# ADC.net
KiCad netlist of a schematic drawn in Altium Designer
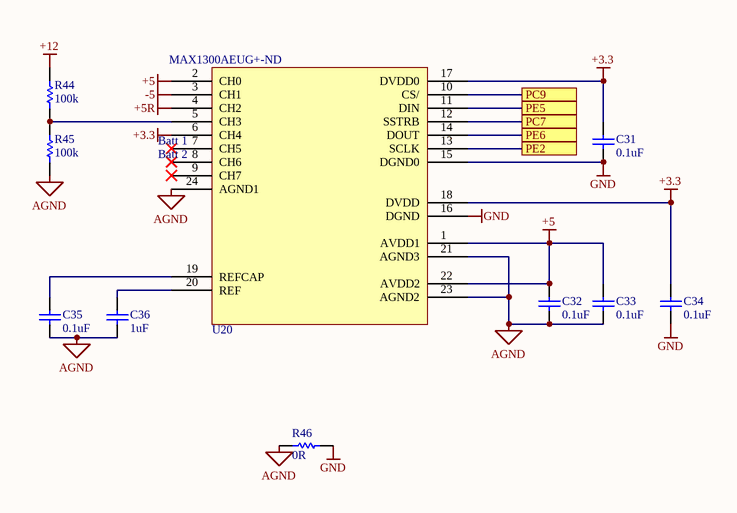
[diagram p0: ADC.SchDoc]

(export (version "E")
  (design (tool "Eeschema 10.0.6"))
  (components
    (comp (ref "C31")
      (value "0.1uF")
      (footprint "CAPC0402(1005)60_L")
      (description "CAP CER 0.1UF 10V X7R 0402")
      (fields
        (field (name "MANUFACTURER") "Murata Electronics North America")
        (field (name "MANUFACTURER PART NUMBER") "GRM155R71A104KA01D")
      )
      (libsource (lib "Altium Content Vault") (part "CMP-1034-00252-1"))
    )
    (comp (ref "C32")
      (value "0.1uF")
      (footprint "CAPC0402(1005)60_L")
      (description "CAP CER 0.1UF 10V X7R 0402")
      (fields
        (field (name "MANUFACTURER") "Murata Electronics North America")
        (field (name "MANUFACTURER PART NUMBER") "GRM155R71A104KA01D")
      )
      (libsource (lib "Altium Content Vault") (part "CMP-1034-00252-1"))
    )
    (comp (ref "C33")
      (value "0.1uF")
      (footprint "CAPC0402(1005)60_L")
      (description "CAP CER 0.1UF 10V X7R 0402")
      (fields
        (field (name "MANUFACTURER") "Murata Electronics North America")
        (field (name "MANUFACTURER PART NUMBER") "GRM155R71A104KA01D")
      )
      (libsource (lib "Altium Content Vault") (part "CMP-1034-00252-1"))
    )
    (comp (ref "C34")
      (value "0.1uF")
      (footprint "CAPC0402(1005)60_L")
      (description "CAP CER 0.1UF 10V X7R 0402")
      (fields
        (field (name "MANUFACTURER") "Murata Electronics North America")
        (field (name "MANUFACTURER PART NUMBER") "GRM155R71A104KA01D")
      )
      (libsource (lib "Altium Content Vault") (part "CMP-1034-00252-1"))
    )
    (comp (ref "C35")
      (value "0.1uF")
      (footprint "CAPC0402(1005)60_L")
      (description "CAP CER 0.1UF 10V X7R 0402")
      (fields
        (field (name "MANUFACTURER") "Murata Electronics North America")
        (field (name "MANUFACTURER PART NUMBER") "GRM155R71A104KA01D")
      )
      (libsource (lib "Altium Content Vault") (part "CMP-1034-00252-1"))
    )
    (comp (ref "C36")
      (value "1uF")
      (footprint "CAPC0402(1005)60_L")
      (description "1µF ±10% 16V Ceramic Capacitor X5R 0402 (1005 Metric)")
      (fields
        (field (name "MANUFACTURER") "Samsung")
        (field (name "MANUFACTURER PART NUMBER") "CL05A105KO5NNNC")
      )
      (libsource (lib "Altium Content Vault") (part "CMP-1034-00252-1"))
    )
    (comp (ref "R44")
      (value "100k")
      (footprint "RESC0402(1005)_M")
      (description "100k 0.063W 1% 0402 (1005 Metric)  SMD")
      (fields
        (field (name "MANUFACTURER") "Panasonic")
        (field (name "MANUFACTURER PART NUMBER") "ERJ-2RKF1003X")
      )
      (libsource (lib "Altium Content Vault") (part "RES"))
    )
    (comp (ref "R45")
      (value "100k")
      (footprint "RESC0402(1005)_M")
      (description "100k 0.063W 1% 0402 (1005 Metric)  SMD")
      (fields
        (field (name "MANUFACTURER") "Panasonic")
        (field (name "MANUFACTURER PART NUMBER") "ERJ-2RKF1003X")
      )
      (libsource (lib "Altium Content Vault") (part "RES"))
    )
    (comp (ref "R46")
      (value "0R")
      (footprint "RESC1005X40X25NL05T10")
      (description "RES SMD 0 OHM JUMPER 1/16W 0402")
      (fields (field (name "MANUFACTURER") "Yageo / Phycomp") (field (name "PART NUMBER") "RC0402JR-070RL"))
      (libsource (lib "Altium Content Vault") (part "RES"))
    )
    (comp (ref "U20")
      (value "MAX1300")
      (footprint "MAX1300")
      (description "IC ADC 16BIT SRL 115KSPS 24TSSOP")
      (fields
        (field (name "SUPPLIER PART NUMBER 1") "MAX1300AEUG+-ND")
        (field (name "MANUFACTURER") "Maxim")
        (field (name "MANUFACTURER PART NUMBER") "MAX1300AEUG+")
      )
      (libsource (lib "ZLS_Schematic_lib") (part "MAX1300"))
    )
  )
  (nets
    (net (code "1") (name "+3.3") (class "Default")
      (node (ref "C31") (pin "2") (pinfunction "2_2") (pintype "passive"))
      (node (ref "C34") (pin "2") (pinfunction "2_2") (pintype "passive"))
      (node (ref "U20") (pin "17") (pinfunction "DVDD0_17") (pintype "passive"))
      (node (ref "U20") (pin "18") (pinfunction "DVDD_18") (pintype "passive"))
      (node (ref "U20") (pin "6") (pinfunction "CH4_6") (pintype "passive"))
    )
    (net (code "2") (name "+5") (class "Default")
      (node (ref "C32") (pin "2") (pinfunction "2_2") (pintype "passive"))
      (node (ref "C33") (pin "2") (pinfunction "2_2") (pintype "passive"))
      (node (ref "U20") (pin "1") (pinfunction "AVDD1_1") (pintype "passive"))
      (node (ref "U20") (pin "2") (pinfunction "CH0_2") (pintype "passive"))
      (node (ref "U20") (pin "22") (pinfunction "AVDD2_22") (pintype "passive"))
    )
    (net (code "3") (name "+5R") (class "Default")
      (node (ref "U20") (pin "4") (pinfunction "CH2_4") (pintype "passive"))
    )
    (net (code "4") (name "+12") (class "Default")
      (node (ref "R44") (pin "2") (pinfunction "2_2") (pintype "passive"))
    )
    (net (code "5") (name "-5") (class "Default")
      (node (ref "U20") (pin "3") (pinfunction "CH1_3") (pintype "passive"))
    )
    (net (code "6") (name "/PC7") (class "Default")
      (node (ref "U20") (pin "12") (pinfunction "SSTRB_12") (pintype "passive"))
    )
    (net (code "7") (name "/PC9") (class "Default")
      (node (ref "U20") (pin "10") (pinfunction "CS/_10") (pintype "passive"))
    )
    (net (code "8") (name "/PE2") (class "Default")
      (node (ref "U20") (pin "13") (pinfunction "SCLK_13") (pintype "passive"))
    )
    (net (code "9") (name "/PE5") (class "Default")
      (node (ref "U20") (pin "11") (pinfunction "DIN_11") (pintype "passive"))
    )
    (net (code "10") (name "/PE6") (class "Default")
      (node (ref "U20") (pin "14") (pinfunction "DOUT_14") (pintype "passive"))
    )
    (net (code "11") (name "AGND") (class "Default")
      (node (ref "C32") (pin "1") (pinfunction "1_1") (pintype "passive"))
      (node (ref "C33") (pin "1") (pinfunction "1_1") (pintype "passive"))
      (node (ref "C35") (pin "1") (pinfunction "1_1") (pintype "passive"))
      (node (ref "C36") (pin "1") (pinfunction "1_1") (pintype "passive"))
      (node (ref "R45") (pin "1") (pinfunction "1_1") (pintype "passive"))
      (node (ref "R46") (pin "1") (pinfunction "1_1") (pintype "passive"))
      (node (ref "U20") (pin "21") (pinfunction "AGND3_21") (pintype "passive"))
      (node (ref "U20") (pin "23") (pinfunction "AGND2_23") (pintype "passive"))
      (node (ref "U20") (pin "24") (pinfunction "AGND1_24") (pintype "passive"))
    )
    (net (code "12") (name "GND") (class "Default")
      (node (ref "C31") (pin "1") (pinfunction "1_1") (pintype "passive"))
      (node (ref "C34") (pin "1") (pinfunction "1_1") (pintype "passive"))
      (node (ref "R46") (pin "2") (pinfunction "2_2") (pintype "passive"))
      (node (ref "U20") (pin "15") (pinfunction "DGND0_15") (pintype "passive"))
      (node (ref "U20") (pin "16") (pinfunction "DGND_16") (pintype "passive"))
    )
    (net (code "13") (name "Net-(U20-CH3)") (class "Default")
      (node (ref "R44") (pin "1") (pinfunction "1_1") (pintype "passive"))
      (node (ref "R45") (pin "2") (pinfunction "2_2") (pintype "passive"))
      (node (ref "U20") (pin "5") (pinfunction "CH3_5") (pintype "passive"))
    )
    (net (code "14") (name "Net-(U20-REF)") (class "Default")
      (node (ref "C36") (pin "2") (pinfunction "2_2") (pintype "passive"))
      (node (ref "U20") (pin "20") (pinfunction "REF_20") (pintype "passive"))
    )
    (net (code "15") (name "Net-(U20-REFCAP)") (class "Default")
      (node (ref "C35") (pin "2") (pinfunction "2_2") (pintype "passive"))
      (node (ref "U20") (pin "19") (pinfunction "REFCAP_19") (pintype "passive"))
    )
    (net (code "16") (name "unconnected-(U20-CH5-Pad7)") (class "Default")
      (node (ref "U20") (pin "7") (pinfunction "CH5_7") (pintype "passive+no_connect"))
    )
    (net (code "17") (name "unconnected-(U20-CH6-Pad8)") (class "Default")
      (node (ref "U20") (pin "8") (pinfunction "CH6_8") (pintype "passive+no_connect"))
    )
    (net (code "18") (name "unconnected-(U20-CH7-Pad9)") (class "Default")
      (node (ref "U20") (pin "9") (pinfunction "CH7_9") (pintype "passive+no_connect"))
    )
  )
)
